# SH2-MCU.net
KiCad netlist of a schematic drawn in Altium Designer
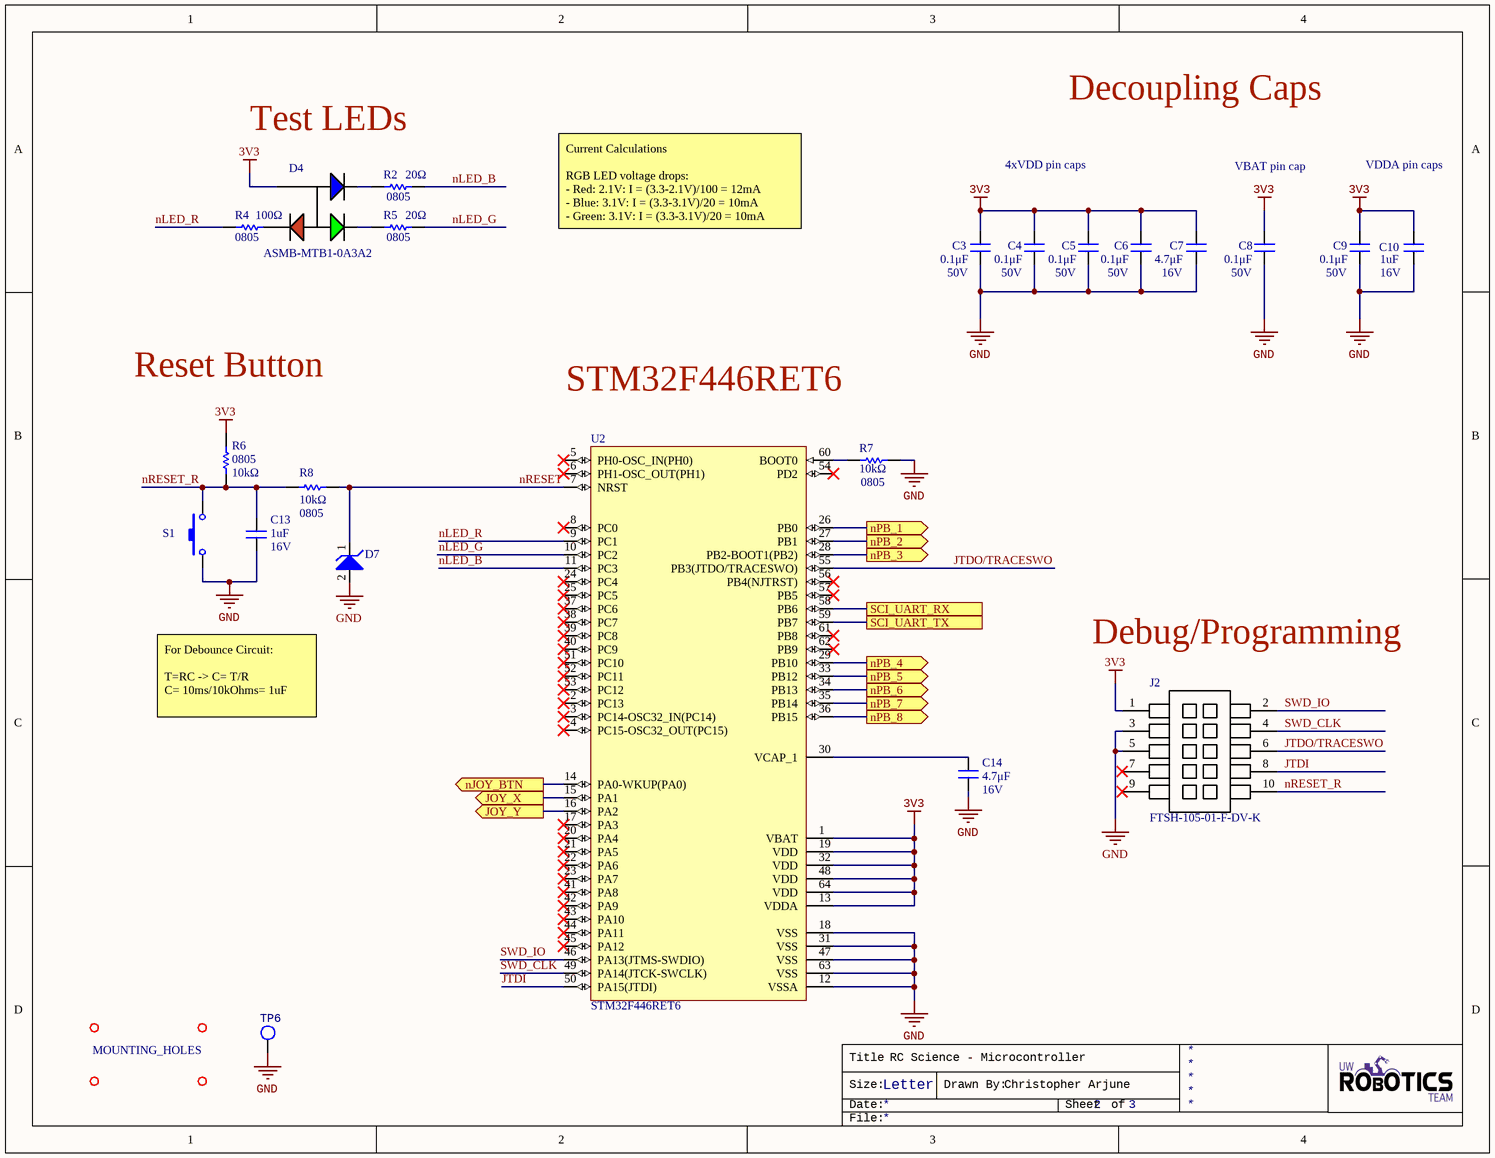
[diagram p0: SH2-MCU.SchDoc]

(export (version "E")
  (design (tool "Eeschema 10.0.6"))
  (components
    (comp (ref "C3")
      (value "0.1μF")
      (footprint "CAPC2012X140N")
      (description "CAP CER 0.1UF 50V X7R 0805")
      (fields (field (name "TOLERANCE") "10%") (field (name "VOLTAGE RATING") "50V"))
      (libsource (lib "UWRT_Schematic_Library_2020") (part "CAP_0.1uF_50V_0805"))
    )
    (comp (ref "C4")
      (value "0.1μF")
      (footprint "CAPC2012X140N")
      (description "CAP CER 0.1UF 50V X7R 0805")
      (fields (field (name "TOLERANCE") "10%") (field (name "VOLTAGE RATING") "50V"))
      (libsource (lib "UWRT_Schematic_Library_2020") (part "CAP_0.1uF_50V_0805"))
    )
    (comp (ref "C5")
      (value "0.1μF")
      (footprint "CAPC2012X140N")
      (description "CAP CER 0.1UF 50V X7R 0805")
      (fields (field (name "TOLERANCE") "10%") (field (name "VOLTAGE RATING") "50V"))
      (libsource (lib "UWRT_Schematic_Library_2020") (part "CAP_0.1uF_50V_0805"))
    )
    (comp (ref "C6")
      (value "0.1μF")
      (footprint "CAPC2012X140N")
      (description "CAP CER 0.1UF 50V X7R 0805")
      (fields (field (name "TOLERANCE") "10%") (field (name "VOLTAGE RATING") "50V"))
      (libsource (lib "UWRT_Schematic_Library_2020") (part "CAP_0.1uF_50V_0805"))
    )
    (comp (ref "C7")
      (value "4.7μF")
      (footprint "CAPC2012X140N")
      (description "CAP CER 4.7UF 16V X5R 0805")
      (fields
        (field (name "TOLERANCE") "10%")
        (field (name "VOLTAGE RATING") "16V")
        (field (name "Comment") "CAP_4.7uF_16V_0805")
      )
      (libsource (lib "UWRT_Schematic_Library_2020") (part "CAP_4.7uF_16V_0805"))
    )
    (comp (ref "C8")
      (value "0.1μF")
      (footprint "CAPC2012X140N")
      (description "CAP CER 0.1UF 50V X7R 0805")
      (fields (field (name "TOLERANCE") "10%") (field (name "VOLTAGE RATING") "50V"))
      (libsource (lib "UWRT_Schematic_Library_2020") (part "CAP_0.1uF_50V_0805"))
    )
    (comp (ref "C9")
      (value "0.1μF")
      (footprint "CAPC2012X140N")
      (description "CAP CER 0.1UF 50V X7R 0805")
      (fields (field (name "TOLERANCE") "10%") (field (name "VOLTAGE RATING") "50V"))
      (libsource (lib "UWRT_Schematic_Library_2020") (part "CAP_0.1uF_50V_0805"))
    )
    (comp (ref "C10")
      (value "1uF")
      (footprint "CAPC2012X140N")
      (description "CAP CER 1UF 16V X7R 0805")
      (fields
        (field (name "TOLERANCE") "10%")
        (field (name "VOLTAGE RATING") "16V")
        (field (name "Comment") "CAP_1uF_16V_0805")
      )
      (libsource (lib "UWRT_Schematic_Library_2020") (part "CAP_1uF_16V_0805"))
    )
    (comp (ref "C13")
      (value "1uF")
      (footprint "CAPC2012X140N")
      (description "CAP CER 1UF 16V X7R 0805")
      (fields
        (field (name "TOLERANCE") "10%")
        (field (name "VOLTAGE RATING") "16V")
        (field (name "Comment") "CAP_1uF_16V_0805")
      )
      (libsource (lib "UWRT_Schematic_Library_2020") (part "CAP_1uF_16V_0805"))
    )
    (comp (ref "C14")
      (value "4.7μF")
      (footprint "CAPC2012X140N")
      (description "CAP CER 4.7UF 16V X5R 0805")
      (fields
        (field (name "TOLERANCE") "10%")
        (field (name "VOLTAGE RATING") "16V")
        (field (name "Comment") "CAP_4.7uF_16V_0805")
      )
      (libsource (lib "UWRT_Schematic_Library_2020") (part "CAP_4.7uF_16V_0805"))
    )
    (comp (ref "D4")
      (value "LED_RGB")
      (footprint "LED_RGB")
      (description "LED RGB DIFFUSED 4PLCC SMD")
      (fields (field (name "MANUFACTURER PART NUMBER 1") "ASMB-MTB1-0A3A2"))
      (libsource (lib "UWRT_Schematic_Library_2020") (part "LED_RGB"))
    )
    (comp (ref "D7")
      (value "TVS_DIODE_UNIDIR_3.3V")
      (footprint "SOD523")
      (description "TVS DIODE 3.3V 14.1V SOD523. Used to protect each connector input line going into the MCU.")
      (libsource (lib "UWRT_Schematic_Library_2020") (part "TVS_DIODE_UNIDIR_3.3V"))
    )
    (comp (ref "J2")
      (value "CON_PROGRAMMING")
      (footprint "FTSH-105-01-F-DV-K-P-TR")
      (fields (field (name "MANUFACTURER PART NUMBER 1") "FTSH-105-01-F-DV-K"))
      (libsource (lib "UWRT_Schematic_Library_2020") (part "CON_PROGRAMMING"))
    )
    (comp (ref "MH1")
      (value "MOUNTING_HOLES")
      (footprint "MOUNTING_HOLE")
      (description "6cm x 6cm")
      (libsource (lib "UWRT_Schematic_Library_2020") (part "MOUNTING_HOLES"))
    )
    (comp (ref "MH2")
      (value "MOUNTING_HOLES")
      (footprint "MOUNTING_HOLE")
      (description "6cm x 6cm")
      (libsource (lib "UWRT_Schematic_Library_2020") (part "MOUNTING_HOLES"))
    )
    (comp (ref "MH3")
      (value "MOUNTING_HOLES")
      (footprint "MOUNTING_HOLE")
      (description "6cm x 6cm")
      (libsource (lib "UWRT_Schematic_Library_2020") (part "MOUNTING_HOLES"))
    )
    (comp (ref "MH4")
      (value "MOUNTING_HOLES")
      (footprint "MOUNTING_HOLE")
      (description "6cm x 6cm")
      (libsource (lib "UWRT_Schematic_Library_2020") (part "MOUNTING_HOLES"))
    )
    (comp (ref "R2")
      (value "20Ω")
      (footprint "RESC2012X60N")
      (description "RES SMD 20 OHM 1% 1/8W 0805")
      (fields
        (field (name "CASE CODE (IMPERIAL)") "0805")
        (field (name "TOLERANCE") "1%")
        (field (name "Comment") "RES_20Ω_0805")
      )
      (libsource (lib "UWRT_Schematic_Library_2020") (part "RES_20Ω_0805"))
    )
    (comp (ref "R4")
      (value "100Ω")
      (footprint "RESC2012X60N")
      (description "RES SMD 100 OHM 1% 1/8W 0805")
      (fields (field (name "CASE CODE (IMPERIAL)") "0805") (field (name "Comment") "RES_100Ω_0805"))
      (libsource (lib "UWRT_Schematic_Library_2020") (part "RES_100Ω_0805"))
    )
    (comp (ref "R5")
      (value "20Ω")
      (footprint "RESC2012X60N")
      (description "RES SMD 20 OHM 1% 1/8W 0805")
      (fields
        (field (name "CASE CODE (IMPERIAL)") "0805")
        (field (name "TOLERANCE") "1%")
        (field (name "Comment") "RES_20Ω_0805")
      )
      (libsource (lib "UWRT_Schematic_Library_2020") (part "RES_20Ω_0805"))
    )
    (comp (ref "R6")
      (value "10kΩ")
      (footprint "RESC2012X60N")
      (description "RES SMD 10K OHM 1% 1/8W 0805")
      (fields
        (field (name "CASE CODE (IMPERIAL)") "0805")
        (field (name "TOLERANCE") "1%")
        (field (name "Comment") "RES_10kΩ_0805")
      )
      (libsource (lib "UWRT_Schematic_Library_2020") (part "RES_10kΩ_0805"))
    )
    (comp (ref "R7")
      (value "10kΩ")
      (footprint "RESC2012X60N")
      (description "RES SMD 10K OHM 1% 1/8W 0805")
      (fields
        (field (name "CASE CODE (IMPERIAL)") "0805")
        (field (name "TOLERANCE") "1%")
        (field (name "Comment") "RES_10kΩ_0805")
      )
      (libsource (lib "UWRT_Schematic_Library_2020") (part "RES_10kΩ_0805"))
    )
    (comp (ref "R8")
      (value "10kΩ")
      (footprint "RESC2012X60N")
      (description "RES SMD 10K OHM 1% 1/8W 0805")
      (fields
        (field (name "CASE CODE (IMPERIAL)") "0805")
        (field (name "TOLERANCE") "1%")
        (field (name "Comment") "RES_10kΩ_0805")
      )
      (libsource (lib "UWRT_Schematic_Library_2020") (part "RES_10kΩ_0805"))
    )
    (comp (ref "S1")
      (value "SW_TACTILE")
      (footprint "B3U-1000P")
      (description "Tactile Switch (Grey)")
      (libsource (lib "UWRT_Schematic_Library_2020") (part "SW_TACTILE"))
    )
    (comp (ref "TP6")
      (value "TESTPOINT_LOOP")
      (footprint "TESTPOINT_LOOP")
      (description "Loop testpoint through-hole pad")
      (libsource (lib "UWRT_Schematic_Library_2020") (part "TESTPOINT_LOOP"))
    )
    (comp (ref "U2")
      (value "STM32F446RET6")
      (footprint "STM-LQFP64_L")
      (libsource (lib "UWRT_Schematic_Library_2020") (part "MCU_STM32F446RET6"))
    )
  )
  (nets
    (net (code "1") (name "/JOY_X") (class "Default")
      (node (ref "U2") (pin "15") (pinfunction "PA1_15") (pintype "bidirectional"))
    )
    (net (code "2") (name "/JOY_Y") (class "Default")
      (node (ref "U2") (pin "16") (pinfunction "PA2_16") (pintype "bidirectional"))
    )
    (net (code "3") (name "/JTDI") (class "Default")
      (node (ref "J2") (pin "8") (pinfunction "8_8") (pintype "passive"))
      (node (ref "U2") (pin "50") (pinfunction "PA15(JTDI)_50") (pintype "bidirectional"))
    )
    (net (code "4") (name "/JTDO{slash}TRACESWO") (class "Default")
      (node (ref "J2") (pin "6") (pinfunction "6_6") (pintype "passive"))
      (node (ref "U2") (pin "55") (pinfunction "PB3(JTDO/TRACESWO)_55") (pintype "bidirectional"))
    )
    (net (code "5") (name "/SCI_UART_RX") (class "Default")
      (node (ref "U2") (pin "58") (pinfunction "PB6_58") (pintype "bidirectional"))
    )
    (net (code "6") (name "/SCI_UART_TX") (class "Default")
      (node (ref "U2") (pin "59") (pinfunction "PB7_59") (pintype "bidirectional"))
    )
    (net (code "7") (name "/SWD_CLK") (class "Default")
      (node (ref "J2") (pin "4") (pinfunction "4_4") (pintype "passive"))
      (node (ref "U2") (pin "49") (pinfunction "PA14(JTCK-SWCLK)_49") (pintype "bidirectional"))
    )
    (net (code "8") (name "/SWD_IO") (class "Default")
      (node (ref "J2") (pin "2") (pinfunction "2_2") (pintype "passive"))
      (node (ref "U2") (pin "46") (pinfunction "PA13(JTMS-SWDIO)_46") (pintype "bidirectional"))
    )
    (net (code "9") (name "/nJOY_BTN") (class "Default")
      (node (ref "U2") (pin "14") (pinfunction "PA0-WKUP(PA0)_14") (pintype "bidirectional"))
    )
    (net (code "10") (name "/nLED_B") (class "Default")
      (node (ref "R2") (pin "2") (pinfunction "2_2") (pintype "passive"))
      (node (ref "U2") (pin "11") (pinfunction "PC3_11") (pintype "bidirectional"))
    )
    (net (code "11") (name "/nLED_G") (class "Default")
      (node (ref "R5") (pin "2") (pinfunction "2_2") (pintype "passive"))
      (node (ref "U2") (pin "10") (pinfunction "PC2_10") (pintype "bidirectional"))
    )
    (net (code "12") (name "/nLED_R") (class "Default")
      (node (ref "R4") (pin "1") (pinfunction "1_1") (pintype "passive"))
      (node (ref "U2") (pin "9") (pinfunction "PC1_9") (pintype "bidirectional"))
    )
    (net (code "13") (name "/nPB_1") (class "Default")
      (node (ref "U2") (pin "26") (pinfunction "PB0_26") (pintype "bidirectional"))
    )
    (net (code "14") (name "/nPB_2") (class "Default")
      (node (ref "U2") (pin "27") (pinfunction "PB1_27") (pintype "bidirectional"))
    )
    (net (code "15") (name "/nPB_3") (class "Default")
      (node (ref "U2") (pin "28") (pinfunction "PB2-BOOT1(PB2)_28") (pintype "bidirectional"))
    )
    (net (code "16") (name "/nPB_4") (class "Default")
      (node (ref "U2") (pin "29") (pinfunction "PB10_29") (pintype "bidirectional"))
    )
    (net (code "17") (name "/nPB_5") (class "Default")
      (node (ref "U2") (pin "33") (pinfunction "PB12_33") (pintype "bidirectional"))
    )
    (net (code "18") (name "/nPB_6") (class "Default")
      (node (ref "U2") (pin "34") (pinfunction "PB13_34") (pintype "bidirectional"))
    )
    (net (code "19") (name "/nPB_7") (class "Default")
      (node (ref "U2") (pin "35") (pinfunction "PB14_35") (pintype "bidirectional"))
    )
    (net (code "20") (name "/nPB_8") (class "Default")
      (node (ref "U2") (pin "36") (pinfunction "PB15_36") (pintype "bidirectional"))
    )
    (net (code "21") (name "/nRESET") (class "Default")
      (node (ref "D7") (pin "1") (pinfunction "1_1") (pintype "passive"))
      (node (ref "R8") (pin "2") (pinfunction "2_2") (pintype "passive"))
      (node (ref "U2") (pin "7") (pinfunction "NRST_7") (pintype "bidirectional"))
    )
    (net (code "22") (name "/nRESET_R") (class "Default")
      (node (ref "C13") (pin "2") (pinfunction "2_2") (pintype "passive"))
      (node (ref "J2") (pin "10") (pinfunction "10_10") (pintype "passive"))
      (node (ref "R6") (pin "1") (pinfunction "1_1") (pintype "passive"))
      (node (ref "R8") (pin "1") (pinfunction "1_1") (pintype "passive"))
      (node (ref "S1") (pin "1") (pinfunction "1_1") (pintype "passive"))
    )
    (net (code "23") (name "3V3") (class "Default")
      (node (ref "C10") (pin "2") (pinfunction "2_2") (pintype "passive"))
      (node (ref "C3") (pin "2") (pinfunction "2_2") (pintype "passive"))
      (node (ref "C4") (pin "2") (pinfunction "2_2") (pintype "passive"))
      (node (ref "C5") (pin "2") (pinfunction "2_2") (pintype "passive"))
      (node (ref "C6") (pin "2") (pinfunction "2_2") (pintype "passive"))
      (node (ref "C7") (pin "2") (pinfunction "2_2") (pintype "passive"))
      (node (ref "C8") (pin "2") (pinfunction "2_2") (pintype "passive"))
      (node (ref "C9") (pin "2") (pinfunction "2_2") (pintype "passive"))
      (node (ref "D4") (pin "4") (pinfunction "9_4") (pintype "passive"))
      (node (ref "J2") (pin "1") (pinfunction "1_1") (pintype "passive"))
      (node (ref "R6") (pin "2") (pinfunction "2_2") (pintype "passive"))
      (node (ref "U2") (pin "1") (pinfunction "VBAT_1") (pintype "power_in"))
      (node (ref "U2") (pin "13") (pinfunction "VDDA_13") (pintype "power_in"))
      (node (ref "U2") (pin "19") (pinfunction "VDD_19") (pintype "power_in"))
      (node (ref "U2") (pin "32") (pinfunction "VDD_32") (pintype "power_in"))
      (node (ref "U2") (pin "48") (pinfunction "VDD_48") (pintype "power_in"))
      (node (ref "U2") (pin "64") (pinfunction "VDD_64") (pintype "power_in"))
    )
    (net (code "24") (name "GND") (class "Default")
      (node (ref "C10") (pin "1") (pinfunction "1_1") (pintype "passive"))
      (node (ref "C13") (pin "1") (pinfunction "1_1") (pintype "passive"))
      (node (ref "C14") (pin "1") (pinfunction "1_1") (pintype "passive"))
      (node (ref "C3") (pin "1") (pinfunction "1_1") (pintype "passive"))
      (node (ref "C4") (pin "1") (pinfunction "1_1") (pintype "passive"))
      (node (ref "C5") (pin "1") (pinfunction "1_1") (pintype "passive"))
      (node (ref "C6") (pin "1") (pinfunction "1_1") (pintype "passive"))
      (node (ref "C7") (pin "1") (pinfunction "1_1") (pintype "passive"))
      (node (ref "C8") (pin "1") (pinfunction "1_1") (pintype "passive"))
      (node (ref "C9") (pin "1") (pinfunction "1_1") (pintype "passive"))
      (node (ref "D7") (pin "2") (pinfunction "2_2") (pintype "passive"))
      (node (ref "J2") (pin "3") (pinfunction "3_3") (pintype "passive"))
      (node (ref "J2") (pin "5") (pinfunction "5_5") (pintype "passive"))
      (node (ref "R7") (pin "2") (pinfunction "2_2") (pintype "passive"))
      (node (ref "S1") (pin "2") (pinfunction "2_2") (pintype "passive"))
      (node (ref "TP6") (pin "1") (pintype "passive"))
      (node (ref "U2") (pin "12") (pinfunction "VSSA_12") (pintype "power_in"))
      (node (ref "U2") (pin "18") (pinfunction "VSS_18") (pintype "power_in"))
      (node (ref "U2") (pin "31") (pinfunction "VSS_31") (pintype "power_in"))
      (node (ref "U2") (pin "47") (pinfunction "VSS_47") (pintype "power_in"))
      (node (ref "U2") (pin "63") (pinfunction "VSS_63") (pintype "power_in"))
    )
    (net (code "25") (name "Net-(D4-10)") (class "Default")
      (node (ref "D4") (pin "3") (pinfunction "10_3") (pintype "passive"))
      (node (ref "R2") (pin "1") (pinfunction "1_1") (pintype "passive"))
    )
    (net (code "26") (name "Net-(D4-11)") (class "Default")
      (node (ref "D4") (pin "1") (pinfunction "11_1") (pintype "passive"))
      (node (ref "R4") (pin "2") (pinfunction "2_2") (pintype "passive"))
    )
    (net (code "27") (name "Net-(D4-12)") (class "Default")
      (node (ref "D4") (pin "2") (pinfunction "12_2") (pintype "passive"))
      (node (ref "R5") (pin "1") (pinfunction "1_1") (pintype "passive"))
    )
    (net (code "28") (name "Net-(U2-BOOT0)") (class "Default")
      (node (ref "R7") (pin "1") (pinfunction "1_1") (pintype "passive"))
      (node (ref "U2") (pin "60") (pinfunction "BOOT0_60") (pintype "input"))
    )
    (net (code "29") (name "Net-(U2-VCAP_1)") (class "Default")
      (node (ref "C14") (pin "2") (pinfunction "2_2") (pintype "passive"))
      (node (ref "U2") (pin "30") (pinfunction "VCAP_1_30") (pintype "passive"))
    )
    (net (code "30") (name "unconnected-(J2-Pad7)") (class "Default")
      (node (ref "J2") (pin "7") (pinfunction "7_7") (pintype "passive+no_connect"))
    )
    (net (code "31") (name "unconnected-(J2-Pad9)") (class "Default")
      (node (ref "J2") (pin "9") (pinfunction "9_9") (pintype "passive+no_connect"))
    )
    (net (code "32") (name "unconnected-(U2-PA3-Pad17)") (class "Default")
      (node (ref "U2") (pin "17") (pinfunction "PA3_17") (pintype "bidirectional+no_connect"))
    )
    (net (code "33") (name "unconnected-(U2-PA4-Pad20)") (class "Default")
      (node (ref "U2") (pin "20") (pinfunction "PA4_20") (pintype "bidirectional+no_connect"))
    )
    (net (code "34") (name "unconnected-(U2-PA5-Pad21)") (class "Default")
      (node (ref "U2") (pin "21") (pinfunction "PA5_21") (pintype "bidirectional+no_connect"))
    )
    (net (code "35") (name "unconnected-(U2-PA6-Pad22)") (class "Default")
      (node (ref "U2") (pin "22") (pinfunction "PA6_22") (pintype "bidirectional+no_connect"))
    )
    (net (code "36") (name "unconnected-(U2-PA7-Pad23)") (class "Default")
      (node (ref "U2") (pin "23") (pinfunction "PA7_23") (pintype "bidirectional+no_connect"))
    )
    (net (code "37") (name "unconnected-(U2-PA8-Pad41)") (class "Default")
      (node (ref "U2") (pin "41") (pinfunction "PA8_41") (pintype "bidirectional+no_connect"))
    )
    (net (code "38") (name "unconnected-(U2-PA9-Pad42)") (class "Default")
      (node (ref "U2") (pin "42") (pinfunction "PA9_42") (pintype "bidirectional+no_connect"))
    )
    (net (code "39") (name "unconnected-(U2-PA10-Pad43)") (class "Default")
      (node (ref "U2") (pin "43") (pinfunction "PA10_43") (pintype "bidirectional+no_connect"))
    )
    (net (code "40") (name "unconnected-(U2-PA11-Pad44)") (class "Default")
      (node (ref "U2") (pin "44") (pinfunction "PA11_44") (pintype "bidirectional+no_connect"))
    )
    (net (code "41") (name "unconnected-(U2-PA12-Pad45)") (class "Default")
      (node (ref "U2") (pin "45") (pinfunction "PA12_45") (pintype "bidirectional+no_connect"))
    )
    (net (code "42") (name "unconnected-(U2-PB4(NJTRST)-Pad56)") (class "Default")
      (node (ref "U2") (pin "56") (pinfunction "PB4(NJTRST)_56") (pintype "bidirectional+no_connect"))
    )
    (net (code "43") (name "unconnected-(U2-PB5-Pad57)") (class "Default")
      (node (ref "U2") (pin "57") (pinfunction "PB5_57") (pintype "bidirectional+no_connect"))
    )
    (net (code "44") (name "unconnected-(U2-PB8-Pad61)") (class "Default")
      (node (ref "U2") (pin "61") (pinfunction "PB8_61") (pintype "bidirectional+no_connect"))
    )
    (net (code "45") (name "unconnected-(U2-PB9-Pad62)") (class "Default")
      (node (ref "U2") (pin "62") (pinfunction "PB9_62") (pintype "bidirectional+no_connect"))
    )
    (net (code "46") (name "unconnected-(U2-PC0-Pad8)") (class "Default")
      (node (ref "U2") (pin "8") (pinfunction "PC0_8") (pintype "bidirectional+no_connect"))
    )
    (net (code "47") (name "unconnected-(U2-PC4-Pad24)") (class "Default")
      (node (ref "U2") (pin "24") (pinfunction "PC4_24") (pintype "bidirectional+no_connect"))
    )
    (net (code "48") (name "unconnected-(U2-PC5-Pad25)") (class "Default")
      (node (ref "U2") (pin "25") (pinfunction "PC5_25") (pintype "bidirectional+no_connect"))
    )
    (net (code "49") (name "unconnected-(U2-PC6-Pad37)") (class "Default")
      (node (ref "U2") (pin "37") (pinfunction "PC6_37") (pintype "bidirectional+no_connect"))
    )
    (net (code "50") (name "unconnected-(U2-PC7-Pad38)") (class "Default")
      (node (ref "U2") (pin "38") (pinfunction "PC7_38") (pintype "bidirectional+no_connect"))
    )
    (net (code "51") (name "unconnected-(U2-PC8-Pad39)") (class "Default")
      (node (ref "U2") (pin "39") (pinfunction "PC8_39") (pintype "bidirectional+no_connect"))
    )
    (net (code "52") (name "unconnected-(U2-PC9-Pad40)") (class "Default")
      (node (ref "U2") (pin "40") (pinfunction "PC9_40") (pintype "bidirectional+no_connect"))
    )
    (net (code "53") (name "unconnected-(U2-PC10-Pad51)") (class "Default")
      (node (ref "U2") (pin "51") (pinfunction "PC10_51") (pintype "bidirectional+no_connect"))
    )
    (net (code "54") (name "unconnected-(U2-PC11-Pad52)") (class "Default")
      (node (ref "U2") (pin "52") (pinfunction "PC11_52") (pintype "bidirectional+no_connect"))
    )
    (net (code "55") (name "unconnected-(U2-PC12-Pad53)") (class "Default")
      (node (ref "U2") (pin "53") (pinfunction "PC12_53") (pintype "bidirectional+no_connect"))
    )
    (net (code "56") (name "unconnected-(U2-PC13-Pad2)") (class "Default")
      (node (ref "U2") (pin "2") (pinfunction "PC13_2") (pintype "bidirectional+no_connect"))
    )
    (net (code "57") (name "unconnected-(U2-PC14-OSC32_IN(PC14)-Pad3)") (class "Default")
      (node (ref "U2") (pin "3") (pinfunction "PC14-OSC32_IN(PC14)_3") (pintype "bidirectional+no_connect"))
    )
    (net (code "58") (name "unconnected-(U2-PC15-OSC32_OUT(PC15)-Pad4)") (class "Default")
      (node (ref "U2") (pin "4") (pinfunction "PC15-OSC32_OUT(PC15)_4") (pintype "bidirectional+no_connect"))
    )
    (net (code "59") (name "unconnected-(U2-PD2-Pad54)") (class "Default")
      (node (ref "U2") (pin "54") (pinfunction "PD2_54") (pintype "bidirectional+no_connect"))
    )
    (net (code "60") (name "unconnected-(U2-PH0-OSC_IN(PH0)-Pad5)") (class "Default")
      (node (ref "U2") (pin "5") (pinfunction "PH0-OSC_IN(PH0)_5") (pintype "bidirectional+no_connect"))
    )
    (net (code "61") (name "unconnected-(U2-PH1-OSC_OUT(PH1)-Pad6)") (class "Default")
      (node (ref "U2") (pin "6") (pinfunction "PH1-OSC_OUT(PH1)_6") (pintype "bidirectional+no_connect"))
    )
  )
)
